# 2_Implausibilities.net
KiCad netlist of a schematic drawn in Altium Designer
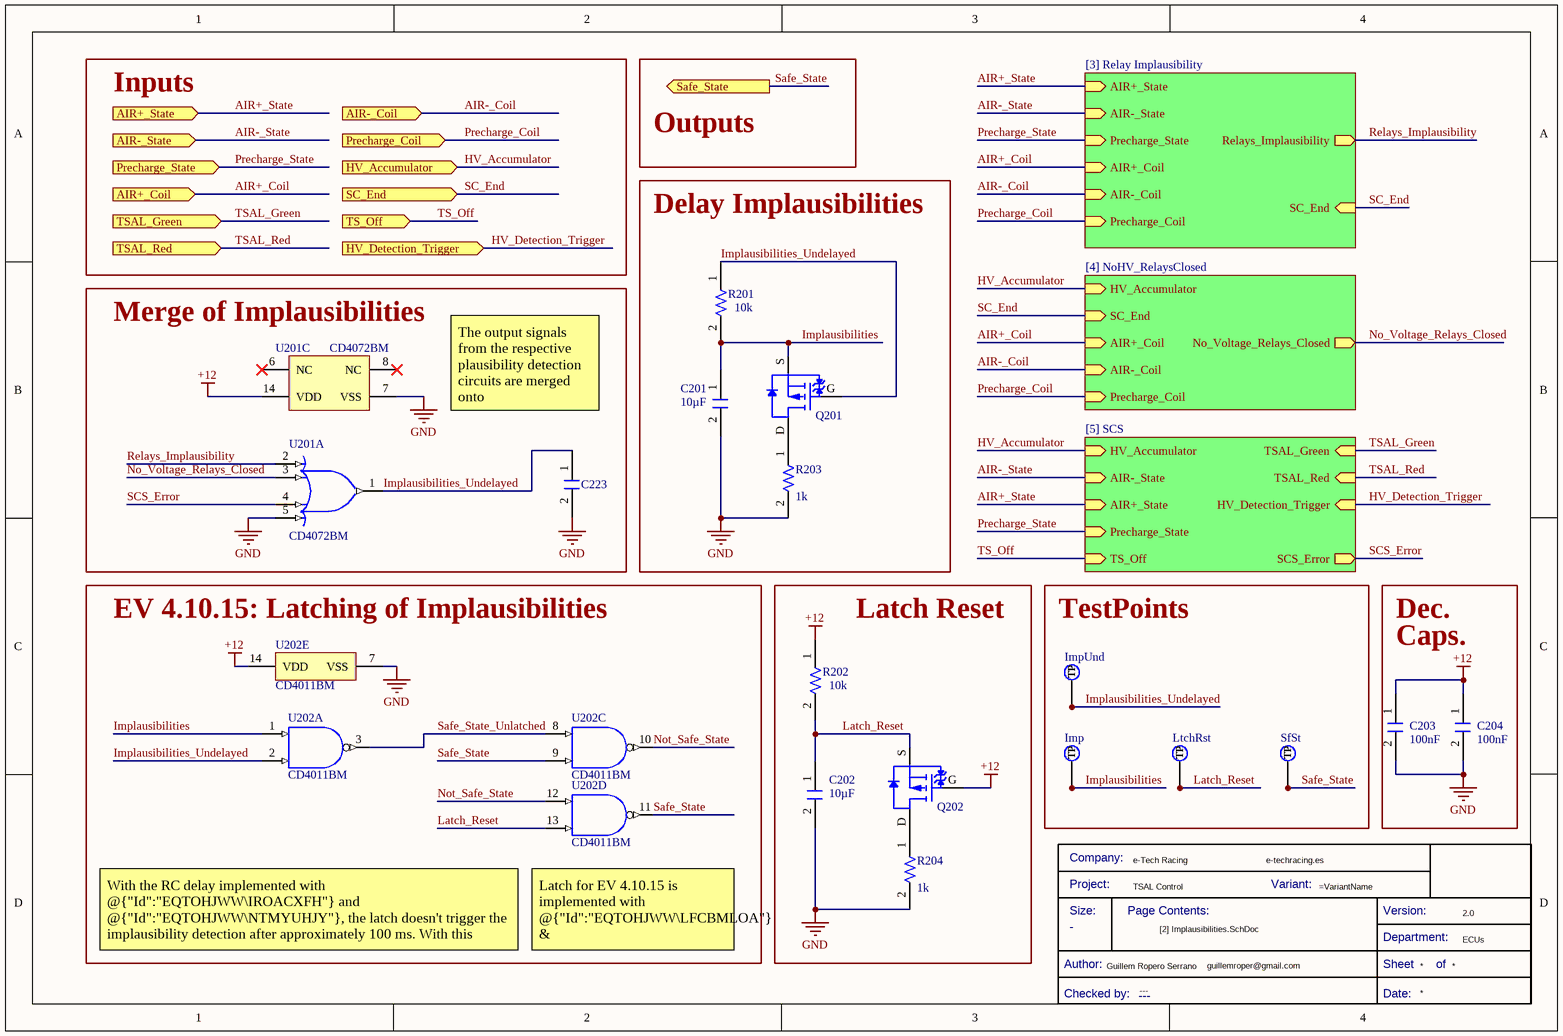
[diagram p0: [2] Implausibilities.SchDoc]

(export (version "E")
  (design (tool "Eeschema 10.0.6"))
  (components
    (comp (ref "C201")
      (value "10µF")
      (footprint "C0805FNPC-R")
      (fields
        (field (name "TOLERANCE") "20%")
        (field (name "Comment") "C10u-16V-0805FNPC-X5R")
        (field (name ".CREATOR") "DR")
      )
      (libsource (lib "EMEA- E-Tech Racing- I'Escola d'Enginyeria de Barcelona Est") (part "C100p-50V-0805FNPC-C0G/NP0"))
    )
    (comp (ref "C202")
      (value "10µF")
      (footprint "C0805FNPC-R")
      (fields
        (field (name "TOLERANCE") "20%")
        (field (name "Comment") "C10u-16V-0805FNPC-X5R")
        (field (name ".CREATOR") "DR")
      )
      (libsource (lib "EMEA- E-Tech Racing- I'Escola d'Enginyeria de Barcelona Est") (part "C100p-50V-0805FNPC-C0G/NP0"))
    )
    (comp (ref "C203")
      (value "100nF")
      (footprint "C0805FNPC-R")
      (description "Cap, 0.1ΜF, 50V, 10%, X7R, 0805")
      (fields
        (field (name "TOLERANCE") "10%")
        (field (name "Comment") "C100n-50V-0805FNPC-X7R")
        (field (name ".CREATOR") "DR")
      )
      (libsource (lib "EMEA- E-Tech Racing- I'Escola d'Enginyeria de Barcelona Est") (part "C100p-50V-0805FNPC-C0G/NP0"))
    )
    (comp (ref "C204")
      (value "100nF")
      (footprint "C0805FNPC-R")
      (description "Cap, 0.1ΜF, 50V, 10%, X7R, 0805")
      (fields
        (field (name "TOLERANCE") "10%")
        (field (name "Comment") "C100n-50V-0805FNPC-X7R")
        (field (name ".CREATOR") "DR")
      )
      (libsource (lib "EMEA- E-Tech Racing- I'Escola d'Enginyeria de Barcelona Est") (part "C100p-50V-0805FNPC-C0G/NP0"))
    )
    (comp (ref "C223")
      (value "C15p-50V-0805FNPC-NP0")
      (footprint "C0805FNPC-R")
      (description "Cap, 15PF, 50V, 5%, C0G/NP0, 0805")
      (fields (field (name "TOLERANCE") "5%") (field (name ".CREATOR") "DR"))
      (libsource (lib "EMEA- E-Tech Racing- I'Escola d'Enginyeria de Barcelona Est") (part "C100p-50V-0805FNPC-C0G/NP0"))
    )
    (comp (ref "Imp")
      (value "TestPoint")
      (footprint "TestPoint")
      (description "Test Point 1x1 mm")
      (fields (field (name ".SCHCHECK") "GP") (field (name ".CREATOR") "GP") (field (name ".PCBCHECK") "GP"))
      (libsource (lib "EMEA- E-Tech Racing- I'Escola d'Enginyeria de Barcelona Est") (part "TestPoint"))
    )
    (comp (ref "ImpUnd")
      (value "TestPoint")
      (footprint "TestPoint")
      (description "Test Point 1x1 mm")
      (fields (field (name ".SCHCHECK") "GP") (field (name ".CREATOR") "GP") (field (name ".PCBCHECK") "GP"))
      (libsource (lib "EMEA- E-Tech Racing- I'Escola d'Enginyeria de Barcelona Est") (part "TestPoint"))
    )
    (comp (ref "LtchRst")
      (value "TestPoint")
      (footprint "TestPoint")
      (description "Test Point 1x1 mm")
      (fields (field (name ".SCHCHECK") "GP") (field (name ".CREATOR") "GP") (field (name ".PCBCHECK") "GP"))
      (libsource (lib "EMEA- E-Tech Racing- I'Escola d'Enginyeria de Barcelona Est") (part "TestPoint"))
    )
    (comp (ref "Q201")
      (value "TRT-PCH-2/30-BSS")
      (footprint "TRT-PCH-2/30-BSS")
      (description "Infineon’s highly innovative OptiMOS™ families include p-channel power MOSFETs, SOT-23-3, RoHS")
      (fields
        (field (name "MANUFACTURER PART NUMBER") "BSS308PEH6327")
        (field (name "MANUFACTURER") "Infineon")
        (field (name ".CREATOR") "DO")
      )
      (libsource (lib "EMEA- E-Tech Racing- I'Escola d'Enginyeria de Barcelona Est") (part "TRT-PCH-2/30-BSS"))
    )
    (comp (ref "Q202")
      (value "TRT-PCH-2/30-BSS")
      (footprint "TRT-PCH-2/30-BSS")
      (description "Infineon’s highly innovative OptiMOS™ families include p-channel power MOSFETs, SOT-23-3, RoHS")
      (fields
        (field (name "MANUFACTURER PART NUMBER") "BSS308PEH6327")
        (field (name "MANUFACTURER") "Infineon")
        (field (name ".CREATOR") "DO")
      )
      (libsource (lib "EMEA- E-Tech Racing- I'Escola d'Enginyeria de Barcelona Est") (part "TRT-PCH-2/30-BSS"))
    )
    (comp (ref "R201")
      (value "10k")
      (footprint "R0805FTK")
      (fields
        (field (name "TOLERANCE") "5%")
        (field (name "Comment") "R10k-0805FTK")
        (field (name ".CREATOR") "DR")
      )
      (libsource (lib "EMEA- E-Tech Racing- I'Escola d'Enginyeria de Barcelona Est") (part "R"))
    )
    (comp (ref "R202")
      (value "10k")
      (footprint "R0805FTK")
      (fields
        (field (name "TOLERANCE") "5%")
        (field (name "Comment") "R10k-0805FTK")
        (field (name ".CREATOR") "DR")
      )
      (libsource (lib "EMEA- E-Tech Racing- I'Escola d'Enginyeria de Barcelona Est") (part "R"))
    )
    (comp (ref "R203")
      (value "1k")
      (footprint "0805")
      (fields
        (field (name "TOLERANCE") "1%")
        (field (name "POWER") "500mW")
        (field (name "Comment") "R1K-0805-0.5W")
      )
      (libsource (lib "EMEA- E-Tech Racing- I'Escola d'Enginyeria de Barcelona Est") (part "R1k-0805"))
    )
    (comp (ref "R204")
      (value "1k")
      (footprint "0805")
      (fields
        (field (name "TOLERANCE") "1%")
        (field (name "POWER") "500mW")
        (field (name "Comment") "R1K-0805-0.5W")
      )
      (libsource (lib "EMEA- E-Tech Racing- I'Escola d'Enginyeria de Barcelona Est") (part "R1k-0805"))
    )
    (comp (ref "SfSt")
      (value "TestPoint")
      (footprint "TestPoint")
      (description "Test Point 1x1 mm")
      (fields (field (name ".SCHCHECK") "GP") (field (name ".CREATOR") "GP") (field (name ".PCBCHECK") "GP"))
      (libsource (lib "EMEA- E-Tech Racing- I'Escola d'Enginyeria de Barcelona Est") (part "TestPoint"))
    )
    (comp (ref "U201")
      (value "CD4072BM")
      (footprint "D0014A_N")
      (description "OR Gate, 4000/14000/40000 Series, 2-Func, 4-Input, CMOS, PDSO14")
      (libsource (lib "EMEA- E-Tech Racing- I'Escola d'Enginyeria de Barcelona Est") (part "TI-CD4072B-14"))
    )
    (comp (ref "U202")
      (value "CD4011BM")
      (footprint "D0014A_N")
      (description "NAND Gate, 4000/14000/40000 Series, 4-Func, 2-Input, CMOS, PDSO14")
      (libsource (lib "EMEA- E-Tech Racing- I'Escola d'Enginyeria de Barcelona Est") (part "TI-NAND-4-2IN-14_A"))
    )
  )
  (nets
    (net (code "1") (name "+12") (class "Default")
      (node (ref "C203") (pin "1") (pinfunction "1_1") (pintype "passive"))
      (node (ref "C204") (pin "1") (pinfunction "1_1") (pintype "passive"))
      (node (ref "Q202") (pin "G") (pinfunction "G_G") (pintype "passive"))
      (node (ref "R202") (pin "1") (pinfunction "1_1") (pintype "passive"))
      (node (ref "U201") (pin "14") (pinfunction "VDD_14") (pintype "power_in"))
      (node (ref "U202") (pin "14") (pinfunction "VDD_14") (pintype "power_in"))
    )
    (net (code "8") (name "/Implausibilities") (class "Default")
      (node (ref "C201") (pin "1") (pinfunction "1_1") (pintype "passive"))
      (node (ref "Imp") (pin "1") (pinfunction "TP_1") (pintype "passive"))
      (node (ref "Q201") (pin "S") (pinfunction "S_S") (pintype "passive"))
      (node (ref "R201") (pin "2") (pinfunction "2_2") (pintype "passive"))
      (node (ref "U202") (pin "1") (pinfunction "A_1") (pintype "input"))
    )
    (net (code "9") (name "/Implausibilities_Undelayed") (class "Default")
      (node (ref "C223") (pin "1") (pinfunction "1_1") (pintype "passive"))
      (node (ref "ImpUnd") (pin "1") (pinfunction "TP_1") (pintype "passive"))
      (node (ref "Q201") (pin "G") (pinfunction "G_G") (pintype "passive"))
      (node (ref "R201") (pin "1") (pinfunction "1_1") (pintype "passive"))
      (node (ref "U201") (pin "1") (pinfunction "J_1") (pintype "output"))
      (node (ref "U202") (pin "2") (pinfunction "B_2") (pintype "input"))
    )
    (net (code "10") (name "/Latch_Reset") (class "Default")
      (node (ref "C202") (pin "1") (pinfunction "1_1") (pintype "passive"))
      (node (ref "LtchRst") (pin "1") (pinfunction "TP_1") (pintype "passive"))
      (node (ref "Q202") (pin "S") (pinfunction "S_S") (pintype "passive"))
      (node (ref "R202") (pin "2") (pinfunction "2_2") (pintype "passive"))
      (node (ref "U202") (pin "13") (pinfunction "H_13") (pintype "input"))
    )
    (net (code "11") (name "/No_Voltage_Relays_Closed") (class "Default")
      (node (ref "U201") (pin "3") (pinfunction "B_3") (pintype "input"))
    )
    (net (code "12") (name "/Not_Safe_State") (class "Default")
      (node (ref "U202") (pin "10") (pinfunction "L_10") (pintype "output"))
      (node (ref "U202") (pin "12") (pinfunction "G_12") (pintype "input"))
    )
    (net (code "15") (name "/Relays_Implausibility") (class "Default")
      (node (ref "U201") (pin "2") (pinfunction "A_2") (pintype "input"))
    )
    (net (code "16") (name "/SCS_Error") (class "Default")
      (node (ref "U201") (pin "4") (pinfunction "C_4") (pintype "input"))
    )
    (net (code "18") (name "/Safe_State") (class "Default")
      (node (ref "SfSt") (pin "1") (pinfunction "TP_1") (pintype "passive"))
      (node (ref "U202") (pin "11") (pinfunction "M_11") (pintype "output"))
      (node (ref "U202") (pin "9") (pinfunction "F_9") (pintype "input"))
    )
    (net (code "19") (name "/Safe_State_Unlatched") (class "Default")
      (node (ref "U202") (pin "3") (pinfunction "J_3") (pintype "output"))
      (node (ref "U202") (pin "8") (pinfunction "E_8") (pintype "input"))
    )
    (net (code "23") (name "GND") (class "Default")
      (node (ref "C201") (pin "2") (pinfunction "2_2") (pintype "passive"))
      (node (ref "C202") (pin "2") (pinfunction "2_2") (pintype "passive"))
      (node (ref "C203") (pin "2") (pinfunction "2_2") (pintype "passive"))
      (node (ref "C204") (pin "2") (pinfunction "2_2") (pintype "passive"))
      (node (ref "C223") (pin "2") (pinfunction "2_2") (pintype "passive"))
      (node (ref "R203") (pin "2") (pinfunction "2_2") (pintype "passive"))
      (node (ref "R204") (pin "2") (pinfunction "2_2") (pintype "passive"))
      (node (ref "U201") (pin "5") (pinfunction "D_5") (pintype "input"))
      (node (ref "U201") (pin "7") (pinfunction "VSS_7") (pintype "power_in"))
      (node (ref "U202") (pin "7") (pinfunction "VSS_7") (pintype "power_in"))
    )
    (net (code "24") (name "Net-(Q201-PadD)") (class "Default")
      (node (ref "Q201") (pin "D") (pinfunction "D_D") (pintype "passive"))
      (node (ref "R203") (pin "1") (pinfunction "1_1") (pintype "passive"))
    )
    (net (code "25") (name "Net-(Q202-PadD)") (class "Default")
      (node (ref "Q202") (pin "D") (pinfunction "D_D") (pintype "passive"))
      (node (ref "R204") (pin "1") (pinfunction "1_1") (pintype "passive"))
    )
    (net (code "26") (name "unconnected-(U201C-NC-Pad6)") (class "Default")
      (node (ref "U201") (pin "6") (pinfunction "NC_6") (pintype "passive+no_connect"))
    )
    (net (code "27") (name "unconnected-(U201C-NC-Pad8)") (class "Default")
      (node (ref "U201") (pin "8") (pinfunction "NC_8") (pintype "passive+no_connect"))
    )
  )
)
